# Summer_Board.net
KiCad netlist of a schematic drawn in EAGLE
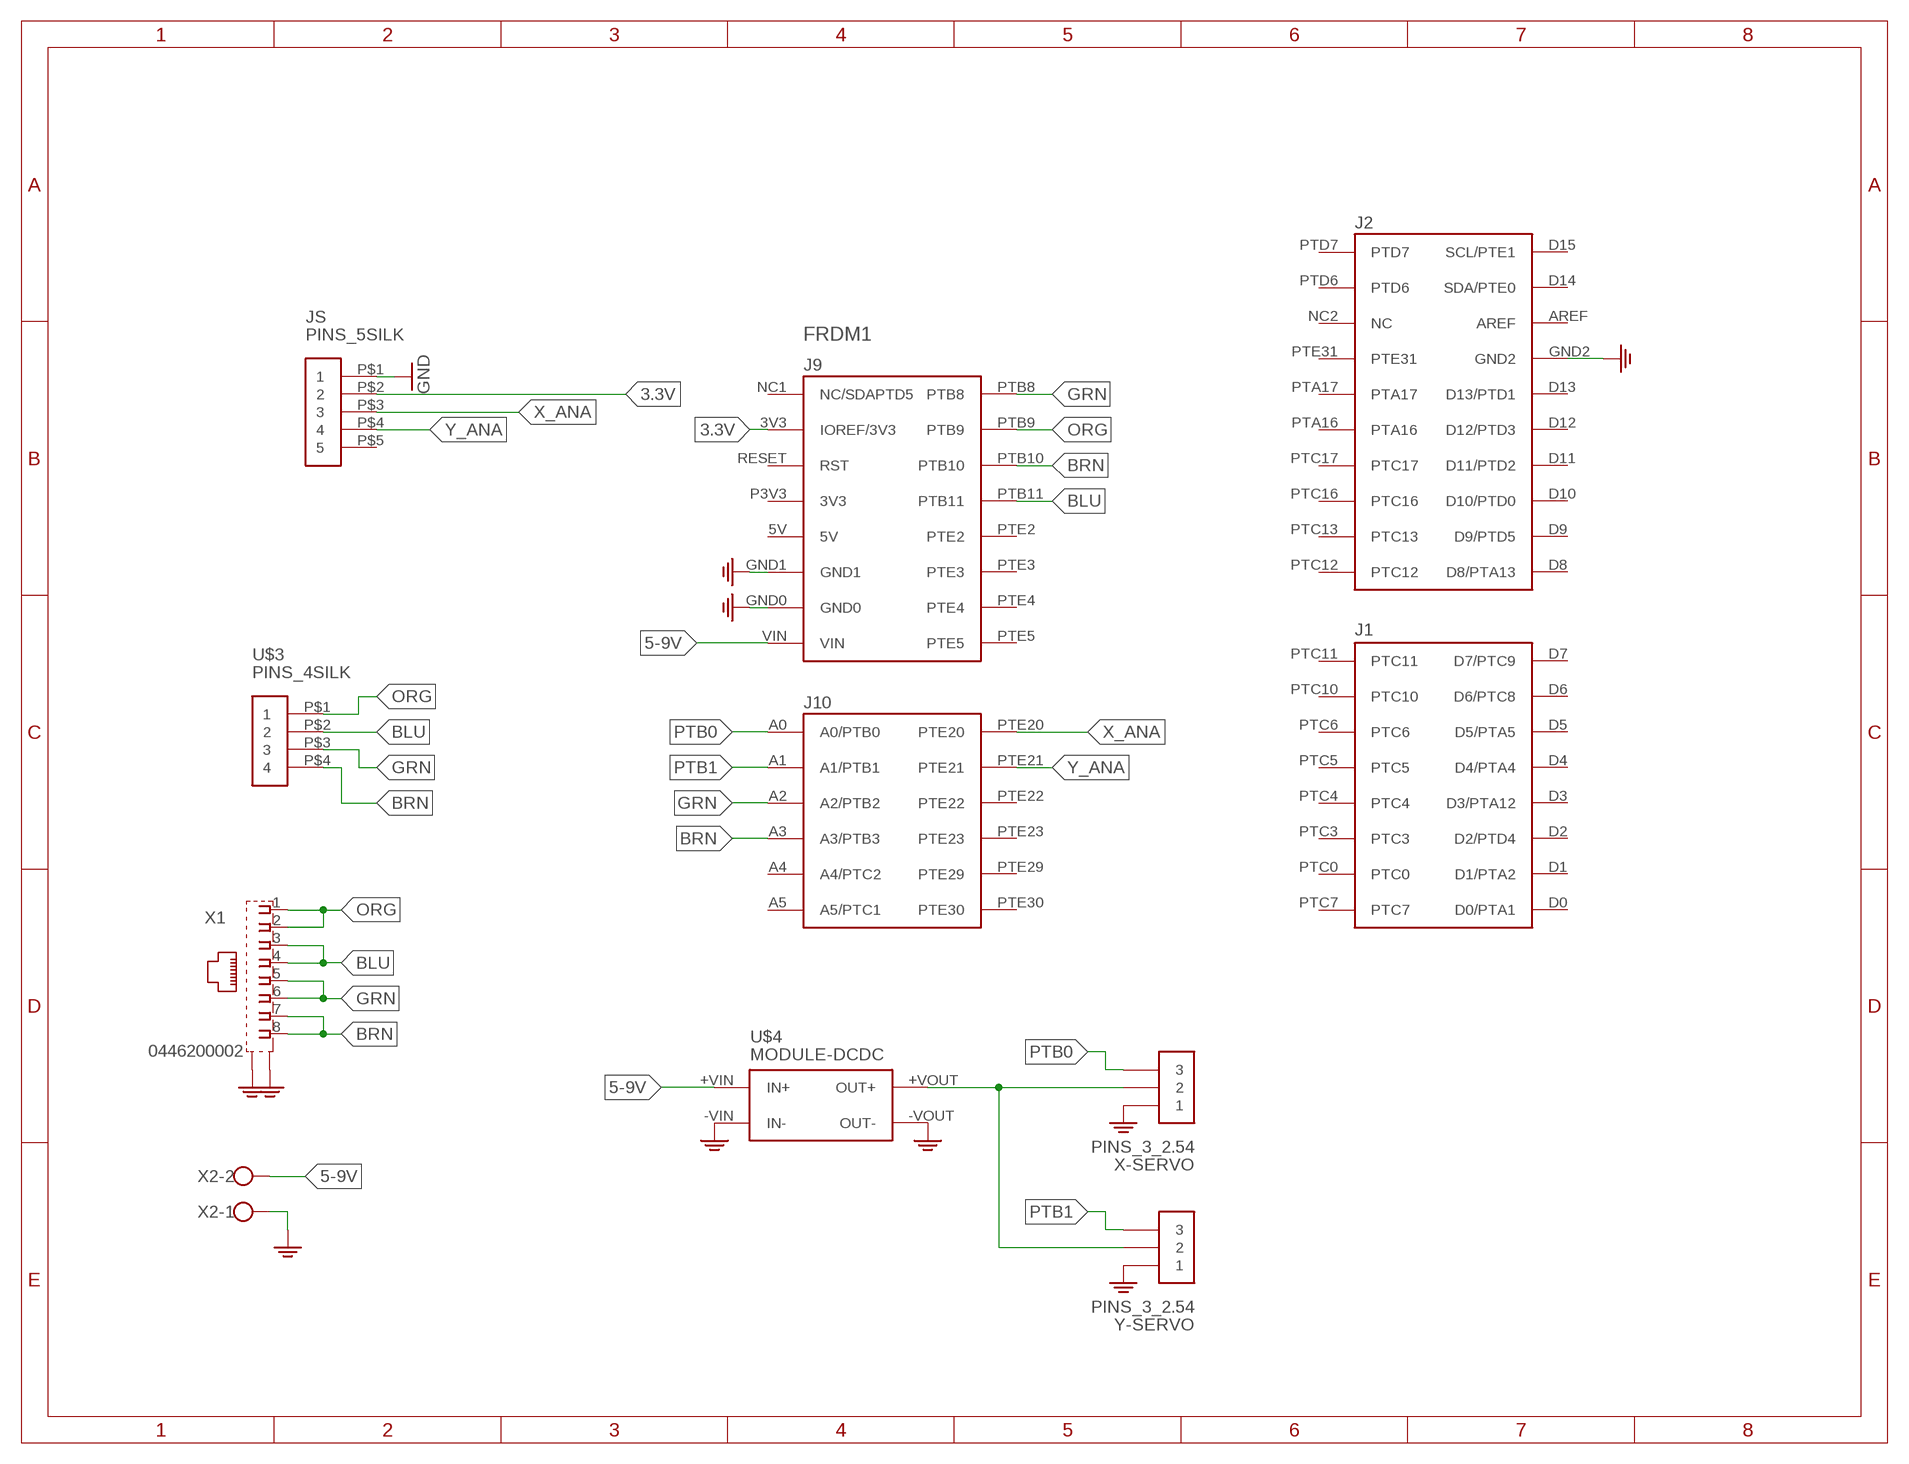
[diagram p0: schematic, sheet 1]

(export (version "E")
  (design (tool "Eeschema 10.0.6"))
  (components
    (comp (ref "FRDM1")
      (value "FRDM-KL25ZNORMAL")
      (footprint "eagle-import:FRDM_KL25Z_NORMAL")
      (libsource (lib "eagle-import") (part "FRDM-KL25ZNORMAL"))
    )
    (comp (ref "JS")
      (value "PINS_5SILK")
      (footprint "eagle-import:PCB_5")
      (libsource (lib "eagle-import") (part "PINS_5SILK"))
    )
    (comp (ref "U$3")
      (value "PINS_4SILK")
      (footprint "eagle-import:PCB_4")
      (libsource (lib "eagle-import") (part "PINS_4SILK"))
    )
    (comp (ref "U$4")
      (value "MODULE-DCDC")
      (footprint "eagle-import:DCDC_CONVERTER_MH")
      (libsource (lib "eagle-import") (part "MODULE-DCDC"))
    )
    (comp (ref "X-SERVO")
      (value "PINS_3_2.54")
      (footprint "eagle-import:PINS_3")
      (libsource (lib "eagle-import") (part "PINS_3_2.54"))
    )
    (comp (ref "X1")
      (value "0446200002")
      (footprint "eagle-import:0446200002")
      (fields (field (name "MF") "MOLEX"))
      (libsource (lib "eagle-import") (part "0446200002"))
    )
    (comp (ref "X2")
      (value "W237-102")
      (footprint "eagle-import:W237-102")
      (fields (field (name "MPN") "237-102"))
      (libsource (lib "eagle-import") (part "W237-102"))
    )
    (comp (ref "Y-SERVO")
      (value "PINS_3_2.54")
      (footprint "eagle-import:PINS_3")
      (libsource (lib "eagle-import") (part "PINS_3_2.54"))
    )
  )
  (nets
    (net (code "1") (name "3.3V") (class "Default")
      (node (ref "FRDM1") (pin "3V3") (pinfunction "IOREF/3V3_3V3") (pintype "bidirectional"))
      (node (ref "JS") (pin "P$2") (pinfunction "2_P$2") (pintype "bidirectional"))
    )
    (net (code "2") (name "5-9V") (class "Default")
      (node (ref "FRDM1") (pin "VIN") (pinfunction "VIN_VIN") (pintype "bidirectional"))
      (node (ref "U$4") (pin "+VIN") (pinfunction "IN+_+VIN") (pintype "bidirectional"))
      (node (ref "X2") (pin "2") (pinfunction "KL_2") (pintype "passive"))
    )
    (net (code "3") (name "BLU") (class "Default")
      (node (ref "FRDM1") (pin "PTB11") (pinfunction "PTB11_PTB11") (pintype "bidirectional"))
      (node (ref "U$3") (pin "P$2") (pinfunction "2_P$2") (pintype "bidirectional"))
      (node (ref "X1") (pin "3") (pinfunction "3_3") (pintype "passive"))
      (node (ref "X1") (pin "4") (pinfunction "4_4") (pintype "passive"))
    )
    (net (code "4") (name "BRN") (class "Default")
      (node (ref "FRDM1") (pin "A3") (pinfunction "A3/PTB3_A3") (pintype "bidirectional"))
      (node (ref "FRDM1") (pin "PTB10") (pinfunction "PTB10_PTB10") (pintype "bidirectional"))
      (node (ref "U$3") (pin "P$4") (pinfunction "4_P$4") (pintype "bidirectional"))
      (node (ref "X1") (pin "7") (pinfunction "7_7") (pintype "passive"))
      (node (ref "X1") (pin "8") (pinfunction "8_8") (pintype "passive"))
    )
    (net (code "5") (name "GND") (class "Default")
      (node (ref "FRDM1") (pin "GND0") (pinfunction "GND0_GND0") (pintype "bidirectional"))
      (node (ref "FRDM1") (pin "GND1") (pinfunction "GND1_GND1") (pintype "bidirectional"))
      (node (ref "FRDM1") (pin "GND2") (pinfunction "GND2_GND2") (pintype "bidirectional"))
      (node (ref "JS") (pin "P$1") (pinfunction "1_P$1") (pintype "bidirectional"))
      (node (ref "U$4") (pin "-VIN") (pinfunction "IN-_-VIN") (pintype "bidirectional"))
      (node (ref "U$4") (pin "-VOUT") (pinfunction "OUT-_-VOUT") (pintype "bidirectional"))
      (node (ref "X-SERVO") (pin "1") (pinfunction "1_1") (pintype "bidirectional"))
      (node (ref "X1") (pin "S@1") (pinfunction "S1_S@1") (pintype "passive"))
      (node (ref "X1") (pin "S@2") (pinfunction "S2_S@2") (pintype "passive"))
      (node (ref "X2") (pin "1") (pinfunction "KL_1") (pintype "passive"))
      (node (ref "Y-SERVO") (pin "1") (pinfunction "1_1") (pintype "bidirectional"))
    )
    (net (code "6") (name "GRN") (class "Default")
      (node (ref "FRDM1") (pin "A2") (pinfunction "A2/PTB2_A2") (pintype "bidirectional"))
      (node (ref "FRDM1") (pin "PTB8") (pinfunction "PTB8_PTB8") (pintype "bidirectional"))
      (node (ref "U$3") (pin "P$3") (pinfunction "3_P$3") (pintype "bidirectional"))
      (node (ref "X1") (pin "5") (pinfunction "5_5") (pintype "passive"))
      (node (ref "X1") (pin "6") (pinfunction "6_6") (pintype "passive"))
    )
    (net (code "7") (name "Net-(U$4-OUT+)") (class "Default")
      (node (ref "U$4") (pin "+VOUT") (pinfunction "OUT+_+VOUT") (pintype "bidirectional"))
      (node (ref "X-SERVO") (pin "2") (pinfunction "2_2") (pintype "bidirectional"))
      (node (ref "Y-SERVO") (pin "2") (pinfunction "2_2") (pintype "bidirectional"))
    )
    (net (code "8") (name "ORG") (class "Default")
      (node (ref "FRDM1") (pin "PTB9") (pinfunction "PTB9_PTB9") (pintype "bidirectional"))
      (node (ref "U$3") (pin "P$1") (pinfunction "1_P$1") (pintype "bidirectional"))
      (node (ref "X1") (pin "1") (pinfunction "1_1") (pintype "passive"))
      (node (ref "X1") (pin "2") (pinfunction "2_2") (pintype "passive"))
    )
    (net (code "9") (name "PTB0") (class "Default")
      (node (ref "FRDM1") (pin "A0") (pinfunction "A0/PTB0_A0") (pintype "bidirectional"))
      (node (ref "X-SERVO") (pin "3") (pinfunction "3_3") (pintype "bidirectional"))
    )
    (net (code "10") (name "PTB1") (class "Default")
      (node (ref "FRDM1") (pin "A1") (pinfunction "A1/PTB1_A1") (pintype "bidirectional"))
      (node (ref "Y-SERVO") (pin "3") (pinfunction "3_3") (pintype "bidirectional"))
    )
    (net (code "11") (name "X_ANA") (class "Default")
      (node (ref "FRDM1") (pin "PTE20") (pinfunction "PTE20_PTE20") (pintype "bidirectional"))
      (node (ref "JS") (pin "P$3") (pinfunction "3_P$3") (pintype "bidirectional"))
    )
    (net (code "12") (name "Y_ANA") (class "Default")
      (node (ref "FRDM1") (pin "PTE21") (pinfunction "PTE21_PTE21") (pintype "bidirectional"))
      (node (ref "JS") (pin "P$4") (pinfunction "4_P$4") (pintype "bidirectional"))
    )
    (net (code "13") (name "unconnected-(FRDM1-3V3-PadP3V3)") (class "Default")
      (node (ref "FRDM1") (pin "P3V3") (pinfunction "3V3_P3V3") (pintype "bidirectional"))
    )
    (net (code "14") (name "unconnected-(FRDM1-A4{slash}PTC2-PadA4)") (class "Default")
      (node (ref "FRDM1") (pin "A4") (pinfunction "A4/PTC2_A4") (pintype "bidirectional"))
    )
    (net (code "15") (name "unconnected-(FRDM1-A5{slash}PTC1-PadA5)") (class "Default")
      (node (ref "FRDM1") (pin "A5") (pinfunction "A5/PTC1_A5") (pintype "bidirectional"))
    )
    (net (code "16") (name "unconnected-(FRDM1-D0{slash}PTA1-PadD0)") (class "Default")
      (node (ref "FRDM1") (pin "D0") (pinfunction "D0/PTA1_D0") (pintype "bidirectional"))
    )
    (net (code "17") (name "unconnected-(FRDM1-D1{slash}PTA2-PadD1)") (class "Default")
      (node (ref "FRDM1") (pin "D1") (pinfunction "D1/PTA2_D1") (pintype "bidirectional"))
    )
    (net (code "18") (name "unconnected-(FRDM1-D2{slash}PTD4-PadD2)") (class "Default")
      (node (ref "FRDM1") (pin "D2") (pinfunction "D2/PTD4_D2") (pintype "bidirectional"))
    )
    (net (code "19") (name "unconnected-(FRDM1-D3{slash}PTA12-PadD3)") (class "Default")
      (node (ref "FRDM1") (pin "D3") (pinfunction "D3/PTA12_D3") (pintype "bidirectional"))
    )
    (net (code "20") (name "unconnected-(FRDM1-D4{slash}PTA4-PadD4)") (class "Default")
      (node (ref "FRDM1") (pin "D4") (pinfunction "D4/PTA4_D4") (pintype "bidirectional"))
    )
    (net (code "21") (name "unconnected-(FRDM1-D5{slash}PTA5-PadD5)") (class "Default")
      (node (ref "FRDM1") (pin "D5") (pinfunction "D5/PTA5_D5") (pintype "bidirectional"))
    )
    (net (code "22") (name "unconnected-(FRDM1-D6{slash}PTC8-PadD6)") (class "Default")
      (node (ref "FRDM1") (pin "D6") (pinfunction "D6/PTC8_D6") (pintype "bidirectional"))
    )
    (net (code "23") (name "unconnected-(FRDM1-D7{slash}PTC9-PadD7)") (class "Default")
      (node (ref "FRDM1") (pin "D7") (pinfunction "D7/PTC9_D7") (pintype "bidirectional"))
    )
    (net (code "24") (name "unconnected-(FRDM1-D8{slash}PTA13-PadD8)") (class "Default")
      (node (ref "FRDM1") (pin "D8") (pinfunction "D8/PTA13_D8") (pintype "bidirectional"))
    )
    (net (code "25") (name "unconnected-(FRDM1-D9{slash}PTD5-PadD9)") (class "Default")
      (node (ref "FRDM1") (pin "D9") (pinfunction "D9/PTD5_D9") (pintype "bidirectional"))
    )
    (net (code "26") (name "unconnected-(FRDM1-D10{slash}PTD0-PadD10)") (class "Default")
      (node (ref "FRDM1") (pin "D10") (pinfunction "D10/PTD0_D10") (pintype "bidirectional"))
    )
    (net (code "27") (name "unconnected-(FRDM1-D11{slash}PTD2-PadD11)") (class "Default")
      (node (ref "FRDM1") (pin "D11") (pinfunction "D11/PTD2_D11") (pintype "bidirectional"))
    )
    (net (code "28") (name "unconnected-(FRDM1-D12{slash}PTD3-PadD12)") (class "Default")
      (node (ref "FRDM1") (pin "D12") (pinfunction "D12/PTD3_D12") (pintype "bidirectional"))
    )
    (net (code "29") (name "unconnected-(FRDM1-D13{slash}PTD1-PadD13)") (class "Default")
      (node (ref "FRDM1") (pin "D13") (pinfunction "D13/PTD1_D13") (pintype "bidirectional"))
    )
    (net (code "30") (name "unconnected-(FRDM1-NC-PadNC2)") (class "Default")
      (node (ref "FRDM1") (pin "NC2") (pinfunction "NC_NC2") (pintype "bidirectional"))
    )
    (net (code "31") (name "unconnected-(FRDM1-NC{slash}SDAPTD5-PadNC1)") (class "Default")
      (node (ref "FRDM1") (pin "NC1") (pinfunction "NC/SDAPTD5_NC1") (pintype "bidirectional"))
    )
    (net (code "32") (name "unconnected-(FRDM1-Pad5V)") (class "Default")
      (node (ref "FRDM1") (pin "5V") (pinfunction "5V_5V") (pintype "bidirectional"))
    )
    (net (code "33") (name "unconnected-(FRDM1-PadAREF)") (class "Default")
      (node (ref "FRDM1") (pin "AREF") (pinfunction "AREF_AREF") (pintype "bidirectional"))
    )
    (net (code "34") (name "unconnected-(FRDM1-PadPTA16)") (class "Default")
      (node (ref "FRDM1") (pin "PTA16") (pinfunction "PTA16_PTA16") (pintype "bidirectional"))
    )
    (net (code "35") (name "unconnected-(FRDM1-PadPTA17)") (class "Default")
      (node (ref "FRDM1") (pin "PTA17") (pinfunction "PTA17_PTA17") (pintype "bidirectional"))
    )
    (net (code "36") (name "unconnected-(FRDM1-PadPTC0)") (class "Default")
      (node (ref "FRDM1") (pin "PTC0") (pinfunction "PTC0_PTC0") (pintype "bidirectional"))
    )
    (net (code "37") (name "unconnected-(FRDM1-PadPTC3)") (class "Default")
      (node (ref "FRDM1") (pin "PTC3") (pinfunction "PTC3_PTC3") (pintype "bidirectional"))
    )
    (net (code "38") (name "unconnected-(FRDM1-PadPTC4)") (class "Default")
      (node (ref "FRDM1") (pin "PTC4") (pinfunction "PTC4_PTC4") (pintype "bidirectional"))
    )
    (net (code "39") (name "unconnected-(FRDM1-PadPTC5)") (class "Default")
      (node (ref "FRDM1") (pin "PTC5") (pinfunction "PTC5_PTC5") (pintype "bidirectional"))
    )
    (net (code "40") (name "unconnected-(FRDM1-PadPTC6)") (class "Default")
      (node (ref "FRDM1") (pin "PTC6") (pinfunction "PTC6_PTC6") (pintype "bidirectional"))
    )
    (net (code "41") (name "unconnected-(FRDM1-PadPTC7)") (class "Default")
      (node (ref "FRDM1") (pin "PTC7") (pinfunction "PTC7_PTC7") (pintype "bidirectional"))
    )
    (net (code "42") (name "unconnected-(FRDM1-PadPTC10)") (class "Default")
      (node (ref "FRDM1") (pin "PTC10") (pinfunction "PTC10_PTC10") (pintype "bidirectional"))
    )
    (net (code "43") (name "unconnected-(FRDM1-PadPTC11)") (class "Default")
      (node (ref "FRDM1") (pin "PTC11") (pinfunction "PTC11_PTC11") (pintype "bidirectional"))
    )
    (net (code "44") (name "unconnected-(FRDM1-PadPTC12)") (class "Default")
      (node (ref "FRDM1") (pin "PTC12") (pinfunction "PTC12_PTC12") (pintype "bidirectional"))
    )
    (net (code "45") (name "unconnected-(FRDM1-PadPTC13)") (class "Default")
      (node (ref "FRDM1") (pin "PTC13") (pinfunction "PTC13_PTC13") (pintype "bidirectional"))
    )
    (net (code "46") (name "unconnected-(FRDM1-PadPTC16)") (class "Default")
      (node (ref "FRDM1") (pin "PTC16") (pinfunction "PTC16_PTC16") (pintype "bidirectional"))
    )
    (net (code "47") (name "unconnected-(FRDM1-PadPTC17)") (class "Default")
      (node (ref "FRDM1") (pin "PTC17") (pinfunction "PTC17_PTC17") (pintype "bidirectional"))
    )
    (net (code "48") (name "unconnected-(FRDM1-PadPTD6)") (class "Default")
      (node (ref "FRDM1") (pin "PTD6") (pinfunction "PTD6_PTD6") (pintype "bidirectional"))
    )
    (net (code "49") (name "unconnected-(FRDM1-PadPTD7)") (class "Default")
      (node (ref "FRDM1") (pin "PTD7") (pinfunction "PTD7_PTD7") (pintype "bidirectional"))
    )
    (net (code "50") (name "unconnected-(FRDM1-PadPTE2)") (class "Default")
      (node (ref "FRDM1") (pin "PTE2") (pinfunction "PTE2_PTE2") (pintype "bidirectional"))
    )
    (net (code "51") (name "unconnected-(FRDM1-PadPTE3)") (class "Default")
      (node (ref "FRDM1") (pin "PTE3") (pinfunction "PTE3_PTE3") (pintype "bidirectional"))
    )
    (net (code "52") (name "unconnected-(FRDM1-PadPTE4)") (class "Default")
      (node (ref "FRDM1") (pin "PTE4") (pinfunction "PTE4_PTE4") (pintype "bidirectional"))
    )
    (net (code "53") (name "unconnected-(FRDM1-PadPTE5)") (class "Default")
      (node (ref "FRDM1") (pin "PTE5") (pinfunction "PTE5_PTE5") (pintype "bidirectional"))
    )
    (net (code "54") (name "unconnected-(FRDM1-PadPTE22)") (class "Default")
      (node (ref "FRDM1") (pin "PTE22") (pinfunction "PTE22_PTE22") (pintype "bidirectional"))
    )
    (net (code "55") (name "unconnected-(FRDM1-PadPTE23)") (class "Default")
      (node (ref "FRDM1") (pin "PTE23") (pinfunction "PTE23_PTE23") (pintype "bidirectional"))
    )
    (net (code "56") (name "unconnected-(FRDM1-PadPTE29)") (class "Default")
      (node (ref "FRDM1") (pin "PTE29") (pinfunction "PTE29_PTE29") (pintype "bidirectional"))
    )
    (net (code "57") (name "unconnected-(FRDM1-PadPTE30)") (class "Default")
      (node (ref "FRDM1") (pin "PTE30") (pinfunction "PTE30_PTE30") (pintype "bidirectional"))
    )
    (net (code "58") (name "unconnected-(FRDM1-PadPTE31)") (class "Default")
      (node (ref "FRDM1") (pin "PTE31") (pinfunction "PTE31_PTE31") (pintype "bidirectional"))
    )
    (net (code "59") (name "unconnected-(FRDM1-RST-PadRESET)") (class "Default")
      (node (ref "FRDM1") (pin "RESET") (pinfunction "RST_RESET") (pintype "bidirectional"))
    )
    (net (code "60") (name "unconnected-(FRDM1-SCL{slash}PTE1-PadD15)") (class "Default")
      (node (ref "FRDM1") (pin "D15") (pinfunction "SCL/PTE1_D15") (pintype "bidirectional"))
    )
    (net (code "61") (name "unconnected-(FRDM1-SDA{slash}PTE0-PadD14)") (class "Default")
      (node (ref "FRDM1") (pin "D14") (pinfunction "SDA/PTE0_D14") (pintype "bidirectional"))
    )
    (net (code "62") (name "unconnected-(JS-5-PadP$5)") (class "Default")
      (node (ref "JS") (pin "P$5") (pinfunction "5_P$5") (pintype "bidirectional"))
    )
  )
)
